# DS141-1_1-A.net
KiCad netlist of a schematic drawn in Altium Designer
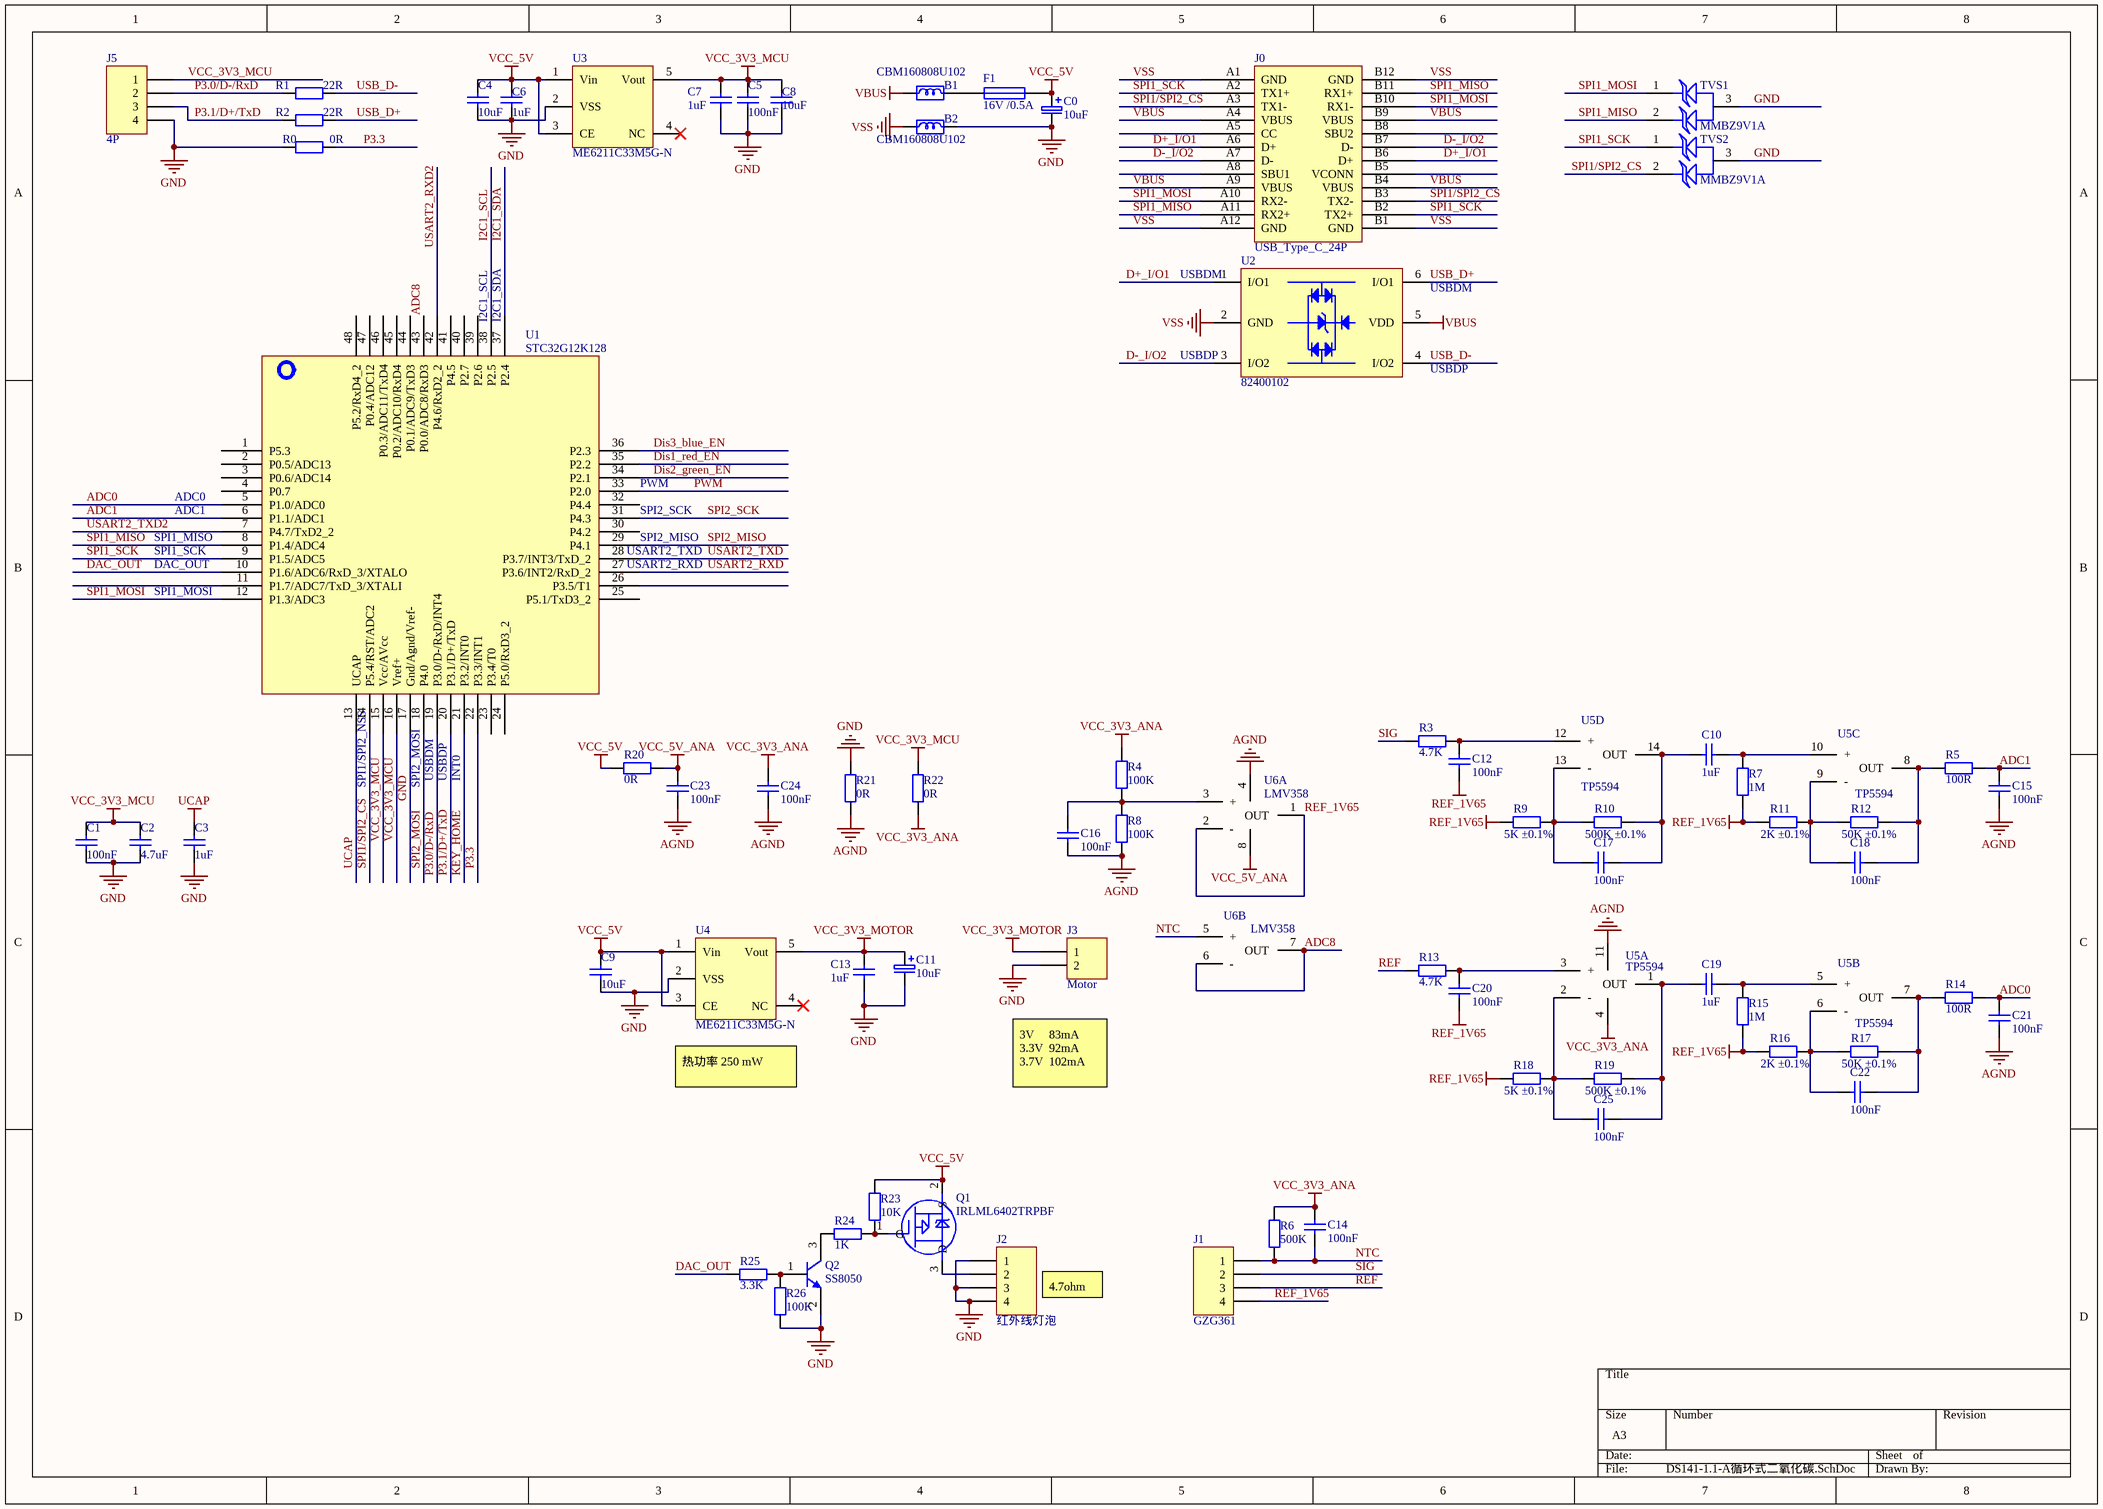
[diagram p0: DS141-1.1-A循环式二氧化碳.SchDoc]

(export (version "E")
  (design (tool "Eeschema 10.0.6"))
  (components
    (comp (ref "B1")
      (value "CBM160808U102")
      (footprint "0603Bead")
      (description "贴片磁珠")
      (libsource (lib "AD_SCH") (part "Chip Ferrite Bead 0606"))
    )
    (comp (ref "B2")
      (value "CBM160808U102")
      (footprint "0603Bead")
      (description "贴片磁珠")
      (libsource (lib "AD_SCH") (part "Chip Ferrite Bead 0606"))
    )
    (comp (ref "C0")
      (value "10uF")
      (footprint "AVX_3216-18(1206)_SMD")
      (description "钽电容")
      (fields (field (name "Comment") "AVX_10uF/16V ±10％(C106)"))
      (libsource (lib "AD_SCH") (part "AVX_10uF/16V ±10％(C106)"))
    )
    (comp (ref "C1")
      (value "100nF")
      (footprint "0603CAP")
      (description "贴片电容")
      (fields (field (name "Comment") "SMDCAP00013"))
      (libsource (lib "AD_SCH") (part "MLCC 100nF 50V ±10％ 0603"))
    )
    (comp (ref "C2")
      (value "4.7uF")
      (footprint "0603CAP")
      (description "贴片电容")
      (fields (field (name "Comment") "SMDCAP00012"))
      (libsource (lib "AD_SCH") (part "MLCC 4.7uF 50V ±10％ 0603"))
    )
    (comp (ref "C3")
      (value "1uF")
      (footprint "0603CAP")
      (description "贴片电容")
      (fields (field (name "Comment") "SMDCAP00015"))
      (libsource (lib "AD_SCH") (part "MLCC 1uF 50V ±10％ 0603"))
    )
    (comp (ref "C4")
      (value "10uF")
      (footprint "1206CAP")
      (description "贴片电容")
      (fields (field (name "Comment") "MLCC 10uF 50V ±20％ 1206"))
      (libsource (lib "AD_SCH") (part "MLCC 10uF 50V ±20％ 1206"))
    )
    (comp (ref "C5")
      (value "100nF")
      (footprint "0603CAP")
      (description "贴片电容")
      (fields (field (name "Comment") "SMDCAP00013"))
      (libsource (lib "AD_SCH") (part "MLCC 100nF 50V ±10％ 0603"))
    )
    (comp (ref "C6")
      (value "1uF")
      (footprint "0603CAP")
      (description "贴片电容")
      (fields (field (name "Comment") "SMDCAP00015"))
      (libsource (lib "AD_SCH") (part "MLCC 1uF 50V ±10％ 0603"))
    )
    (comp (ref "C7")
      (value "1uF")
      (footprint "0603CAP")
      (description "贴片电容")
      (fields (field (name "Comment") "SMDCAP00015"))
      (libsource (lib "AD_SCH") (part "MLCC 1uF 50V ±10％ 0603"))
    )
    (comp (ref "C8")
      (value "10uF")
      (footprint "1206CAP")
      (description "贴片电容")
      (fields (field (name "Comment") "MLCC 10uF 50V ±20％ 1206"))
      (libsource (lib "AD_SCH") (part "MLCC 10uF 50V ±20％ 1206"))
    )
    (comp (ref "C9")
      (value "10uF")
      (footprint "1206CAP")
      (description "贴片电容")
      (fields (field (name "Comment") "MLCC 10uF 50V ±20％ 1206"))
      (libsource (lib "AD_SCH") (part "MLCC 10uF 50V ±20％ 1206"))
    )
    (comp (ref "C10")
      (value "1uF")
      (footprint "0603CAP")
      (description "贴片电容")
      (fields (field (name "Comment") "SMDCAP00015"))
      (libsource (lib "AD_SCH") (part "MLCC 1uF 50V ±10％ 0603"))
    )
    (comp (ref "C11")
      (value "10uF")
      (footprint "AVX_3216-18(1206)_SMD")
      (description "钽电容")
      (fields (field (name "Comment") "AVX_10uF/16V ±10％(C106)"))
      (libsource (lib "AD_SCH") (part "AVX_10uF/16V ±10％(C106)"))
    )
    (comp (ref "C12")
      (value "100nF")
      (footprint "0603CAP")
      (description "贴片电容")
      (fields (field (name "Comment") "SMDCAP00013"))
      (libsource (lib "AD_SCH") (part "MLCC 100nF 50V ±10％ 0603"))
    )
    (comp (ref "C13")
      (value "1uF")
      (footprint "0603CAP")
      (description "贴片电容")
      (fields (field (name "Comment") "SMDCAP00015"))
      (libsource (lib "AD_SCH") (part "MLCC 1uF 50V ±10％ 0603"))
    )
    (comp (ref "C14")
      (value "100nF")
      (footprint "0603CAP")
      (description "贴片电容")
      (fields (field (name "Comment") "SMDCAP00013"))
      (libsource (lib "AD_SCH") (part "MLCC 100nF 50V ±10％ 0603"))
    )
    (comp (ref "C15")
      (value "100nF")
      (footprint "0603CAP")
      (description "贴片电容")
      (fields (field (name "Comment") "SMDCAP00013"))
      (libsource (lib "AD_SCH") (part "MLCC 100nF 50V ±10％ 0603"))
    )
    (comp (ref "C16")
      (value "100nF")
      (footprint "0603CAP")
      (description "贴片电容")
      (fields (field (name "Comment") "SMDCAP00013"))
      (libsource (lib "AD_SCH") (part "MLCC 100nF 50V ±10％ 0603"))
    )
    (comp (ref "C17")
      (value "100nF")
      (footprint "0603CAP")
      (description "贴片电容")
      (fields (field (name "Comment") "SMDCAP00013"))
      (libsource (lib "AD_SCH") (part "MLCC 100nF 50V ±10％ 0603"))
    )
    (comp (ref "C18")
      (value "100nF")
      (footprint "0603CAP")
      (description "贴片电容")
      (fields (field (name "Comment") "SMDCAP00013"))
      (libsource (lib "AD_SCH") (part "MLCC 100nF 50V ±10％ 0603"))
    )
    (comp (ref "C19")
      (value "1uF")
      (footprint "0603CAP")
      (description "贴片电容")
      (fields (field (name "Comment") "SMDCAP00015"))
      (libsource (lib "AD_SCH") (part "MLCC 1uF 50V ±10％ 0603"))
    )
    (comp (ref "C20")
      (value "100nF")
      (footprint "0603CAP")
      (description "贴片电容")
      (fields (field (name "Comment") "SMDCAP00013"))
      (libsource (lib "AD_SCH") (part "MLCC 100nF 50V ±10％ 0603"))
    )
    (comp (ref "C21")
      (value "100nF")
      (footprint "0603CAP")
      (description "贴片电容")
      (fields (field (name "Comment") "SMDCAP00013"))
      (libsource (lib "AD_SCH") (part "MLCC 100nF 50V ±10％ 0603"))
    )
    (comp (ref "C22")
      (value "100nF")
      (footprint "0603CAP")
      (description "贴片电容")
      (fields (field (name "Comment") "SMDCAP00013"))
      (libsource (lib "AD_SCH") (part "MLCC 100nF 50V ±10％ 0603"))
    )
    (comp (ref "C23")
      (value "100nF")
      (footprint "0603CAP")
      (description "贴片电容")
      (fields (field (name "Comment") "SMDCAP00013"))
      (libsource (lib "AD_SCH") (part "MLCC 100nF 50V ±10％ 0603"))
    )
    (comp (ref "C24")
      (value "100nF")
      (footprint "0603CAP")
      (description "贴片电容")
      (fields (field (name "Comment") "SMDCAP00013"))
      (libsource (lib "AD_SCH") (part "MLCC 100nF 50V ±10％ 0603"))
    )
    (comp (ref "C25")
      (value "100nF")
      (footprint "0603CAP")
      (description "贴片电容")
      (fields (field (name "Comment") "SMDCAP00013"))
      (libsource (lib "AD_SCH") (part "MLCC 100nF 50V ±10％ 0603"))
    )
    (comp (ref "F1")
      (value "16V /0.5A")
      (footprint "1206FUSE")
      (description "贴片自恢复保险丝 16V /0.5A")
      (fields (field (name "Comment") "SMD1206-050C-16V"))
      (libsource (lib "AD_SCH") (part "SMD1206-050C-16V"))
    )
    (comp (ref "J0")
      (value "USB_Type_C_24P")
      (footprint "USB_TYPE_C_24P_Receptacle")
      (libsource (lib "AD_SCH") (part "USB_Type_C_24P"))
    )
    (comp (ref "J1")
      (value "GZG361")
      (footprint "CO2_connecet_4p")
      (description "4P弯针座")
      (fields (field (name "Comment") "SL000000034"))
      (libsource (lib "AD_SCH") (part "XH2.54mm-4AW 弯针座"))
    )
    (comp (ref "J2")
      (value "红外线灯泡")
      (footprint "CO2_connecet_4p")
      (description "4P直针座")
      (fields (field (name "Comment") "SL000000029"))
      (libsource (lib "AD_SCH") (part "XH2.54mm-4A 直针座"))
    )
    (comp (ref "J3")
      (value "Motor")
      (footprint "SIP2")
      (description "单排直针")
      (fields (field (name "Comment") "SL000000042"))
      (libsource (lib "AD_SCH") (part "DIP2 单排直针 1*40P 间距2.54mm 针长11mm 铜"))
    )
    (comp (ref "J5")
      (value "4P")
      (footprint "H4")
      (description "单排直针")
      (fields (field (name "Comment") "DIP4单排直针  间距2mm 针长11mm 铜"))
      (libsource (lib "AD_SCH") (part "DIP4单排直针  间距2mm 针长11mm 铜"))
    )
    (comp (ref "Q1")
      (value "IRLML6402TRPBF")
      (footprint "SOT23")
      (description "贴片P-MOS管")
      (fields (field (name "Comment") "SMDPMOS00001"))
      (libsource (lib "AD_SCH") (part "IRLML6402TRPBF SOT-23 IR"))
    )
    (comp (ref "Q2")
      (value "SS8050")
      (footprint "SOT23")
      (description "贴片三极管")
      (fields (field (name "Comment") "SMDNPN00001"))
      (libsource (lib "AD_SCH") (part "SS8050 Y1 SOT-23"))
    )
    (comp (ref "R0")
      (value "0R")
      (footprint "0603RES")
      (description "贴片电阻")
      (fields (field (name "Comment") "Chip 0R 1/16W ±1％ 0603"))
      (libsource (lib "") (part "Chip 0R 1/16W ±1％ 0603_1"))
    )
    (comp (ref "R1")
      (value "22R")
      (footprint "0603RES")
      (description "贴片电阻")
      (fields (field (name "Comment") "Chip 22R 1/16W ±1％ 0603"))
      (libsource (lib "AD_SCH") (part "Chip 22R 1/16W ±1％ 0603"))
    )
    (comp (ref "R2")
      (value "22R")
      (footprint "0603RES")
      (description "贴片电阻")
      (fields (field (name "Comment") "Chip 22R 1/16W ±1％ 0603"))
      (libsource (lib "AD_SCH") (part "Chip 22R 1/16W ±1％ 0603"))
    )
    (comp (ref "R3")
      (value "4.7K")
      (footprint "0603RES")
      (description "贴片电阻")
      (fields (field (name "Comment") "SMDRES00047"))
      (libsource (lib "AD_SCH") (part "Chip 4.7K 1/10W ±1％ 0603"))
    )
    (comp (ref "R4")
      (value "100K")
      (footprint "0603RES")
      (description "贴片电阻")
      (fields (field (name "Comment") "SMDRES00071"))
      (libsource (lib "AD_SCH") (part "Chip 100K 1/16W ±1％ 0603"))
    )
    (comp (ref "R5")
      (value "100R")
      (footprint "0603RES")
      (description "贴片电阻")
      (fields (field (name "Comment") "SMDRES00015"))
      (libsource (lib "AD_SCH") (part "Chip 100R 1/16W ±1％ 0603"))
    )
    (comp (ref "R6")
      (value "500K")
      (footprint "0603RES")
      (fields (field (name "Comment") "Chip 500K 1/10W ±1% 0603"))
      (libsource (lib "AD_SCH") (part "Chip 500K 1/10W ±1% 0603"))
    )
    (comp (ref "R7")
      (value "1M")
      (footprint "0603RES")
      (description "贴片电阻")
      (fields (field (name "Comment") "SMDRES00085"))
      (libsource (lib "AD_SCH") (part "Chip 1M 1/16W ±1％ 0603"))
    )
    (comp (ref "R8")
      (value "100K")
      (footprint "0603RES")
      (description "贴片电阻")
      (fields (field (name "Comment") "SMDRES00071"))
      (libsource (lib "AD_SCH") (part "Chip 100K 1/16W ±1％ 0603"))
    )
    (comp (ref "R9")
      (value "5K ±0.1%")
      (footprint "0603RES")
      (fields (field (name "Comment") "Chip 5K 1/10W ±0.1％ 0603"))
      (libsource (lib "AD_SCH") (part "Chip 5K 1/10W ±0.1％ 0603"))
    )
    (comp (ref "R10")
      (value "500K ±0.1%")
      (footprint "0603RES")
      (fields (field (name "Comment") "Chip 500K 1/10W ±0.1% 0603"))
      (libsource (lib "AD_SCH") (part "Chip 500K 1/10W ±0.1% 0603"))
    )
    (comp (ref "R11")
      (value "2K ±0.1%")
      (footprint "0603RES")
      (fields (field (name "Comment") "Chip 2K 1/10W ±0.1％ 0603"))
      (libsource (lib "AD_SCH") (part "Chip 2K 1/10W ±0.1％ 0603"))
    )
    (comp (ref "R12")
      (value "50K ±0.1%")
      (footprint "0603RES")
      (fields (field (name "Comment") "Chip 50K 1/10W ±0.1％ 0603"))
      (libsource (lib "AD_SCH") (part "Chip 50K 1/10W ±0.1％ 0603"))
    )
    (comp (ref "R13")
      (value "4.7K")
      (footprint "0603RES")
      (description "贴片电阻")
      (fields (field (name "Comment") "SMDRES00047"))
      (libsource (lib "AD_SCH") (part "Chip 4.7K 1/10W ±1％ 0603"))
    )
    (comp (ref "R14")
      (value "100R")
      (footprint "0603RES")
      (description "贴片电阻")
      (fields (field (name "Comment") "SMDRES00015"))
      (libsource (lib "AD_SCH") (part "Chip 100R 1/16W ±1％ 0603"))
    )
    (comp (ref "R15")
      (value "1M")
      (footprint "0603RES")
      (description "贴片电阻")
      (fields (field (name "Comment") "SMDRES00085"))
      (libsource (lib "AD_SCH") (part "Chip 1M 1/16W ±1％ 0603"))
    )
    (comp (ref "R16")
      (value "2K ±0.1%")
      (footprint "0603RES")
      (fields (field (name "Comment") "Chip 2K 1/10W ±0.1％ 0603"))
      (libsource (lib "AD_SCH") (part "Chip 2K 1/10W ±0.1％ 0603"))
    )
    (comp (ref "R17")
      (value "50K ±0.1%")
      (footprint "0603RES")
      (fields (field (name "Comment") "Chip 50K 1/10W ±0.1％ 0603"))
      (libsource (lib "AD_SCH") (part "Chip 50K 1/10W ±0.1％ 0603"))
    )
    (comp (ref "R18")
      (value "5K ±0.1%")
      (footprint "0603RES")
      (fields (field (name "Comment") "Chip 5K 1/10W ±0.1％ 0603"))
      (libsource (lib "AD_SCH") (part "Chip 5K 1/10W ±0.1％ 0603"))
    )
    (comp (ref "R19")
      (value "500K ±0.1%")
      (footprint "0603RES")
      (fields (field (name "Comment") "Chip 500K 1/10W ±0.1% 0603"))
      (libsource (lib "AD_SCH") (part "Chip 500K 1/10W ±0.1% 0603"))
    )
    (comp (ref "R20")
      (value "0R")
      (footprint "0603RES")
      (description "贴片电阻")
      (fields (field (name "Comment") "Chip 0R 1/16W ±1％ 0603"))
      (libsource (lib "") (part "Chip 0R 1/16W ±1％ 0603_1"))
    )
    (comp (ref "R21")
      (value "0R")
      (footprint "0603RES")
      (description "贴片电阻")
      (fields (field (name "Comment") "Chip 0R 1/16W ±1％ 0603"))
      (libsource (lib "AD_SCH") (part "Chip 0R 1/16W ±1％ 0603"))
    )
    (comp (ref "R22")
      (value "0R")
      (footprint "0603RES")
      (description "贴片电阻")
      (fields (field (name "Comment") "Chip 0R 1/16W ±1％ 0603"))
      (libsource (lib "AD_SCH") (part "Chip 0R 1/16W ±1％ 0603"))
    )
    (comp (ref "R23")
      (value "10K")
      (footprint "0603RES")
      (description "贴片电阻")
      (fields (field (name "Comment") "SMDRES00056"))
      (libsource (lib "AD_SCH") (part "Chip 10K 1/16W ±1％ 0603"))
    )
    (comp (ref "R24")
      (value "1K")
      (footprint "0603RES")
      (description "贴片电阻")
      (fields (field (name "Comment") "SMDRES00034"))
      (libsource (lib "AD_SCH") (part "Chip 1K 1/16W ±1％ 0603"))
    )
    (comp (ref "R25")
      (value "3.3K")
      (footprint "0603RES")
      (description "贴片电阻")
      (fields (field (name "Comment") "SMDRES00090"))
      (libsource (lib "AD_SCH") (part "Chip 3.3K 1/16W ±1％ 0603"))
    )
    (comp (ref "R26")
      (value "100K")
      (footprint "0603RES")
      (description "贴片电阻")
      (fields (field (name "Comment") "SMDRES00071"))
      (libsource (lib "") (part "Chip 100K 1/16W ±1％ 0603_1"))
    )
    (comp (ref "TVS1")
      (value "MMBZ9V1A")
      (footprint "SOT23")
      (description "瞬态抑制二极管")
      (libsource (lib "AD_SCH") (part "TVS"))
    )
    (comp (ref "TVS2")
      (value "MMBZ9V1A")
      (footprint "SOT23")
      (description "瞬态抑制二极管")
      (libsource (lib "AD_SCH") (part "TVS"))
    )
    (comp (ref "U1")
      (value "STC32G12K128")
      (footprint "LQFP-48")
      (description "单片机芯片")
      (fields (field (name "Comment") "STC32G12K128_35I LQFP48"))
      (libsource (lib "AD_SCH") (part "STC32G12K128_35I LQFP48"))
    )
    (comp (ref "U2")
      (value "82400102")
      (footprint "SOT23-6")
      (description "瞬态抑制二极管(TVS)")
      (libsource (lib "AD_SCH") (part "82400102"))
    )
    (comp (ref "U3")
      (value "ME6211C33M5G-N")
      (footprint "SOT23-5")
      (description "稳压芯片")
      (libsource (lib "AD_SCH") (part "ME6211C33M5G-N"))
    )
    (comp (ref "U4")
      (value "ME6211C33M5G-N")
      (footprint "SOT23-5")
      (description "稳压芯片")
      (libsource (lib "AD_SCH") (part "ME6211C33M5G-N"))
    )
    (comp (ref "U5")
      (value "TP5594")
      (footprint "TSSOP14")
      (fields (field (name "Comment") "TP5594-TR  TSSOP-14"))
      (libsource (lib "AD_SCH") (part "TP5594-TR  TSSOP-14"))
    )
    (comp (ref "U6")
      (value "LMV358")
      (footprint "VSSOP-8-H-1.1")
      (description "双路、5.5V、1MHz、4mV 失调电压、RRO 运算放大器")
      (fields (field (name "Comment") "LMV358IDGKR  VSSOP-8"))
      (libsource (lib "AD_SCH") (part "LMV358IDGKR  VSSOP-8"))
    )
  )
  (nets
    (net (code "1") (name "/ADC0") (class "Default")
      (node (ref "C21") (pin "1") (pinfunction "1_1") (pintype "passive"))
      (node (ref "R14") (pin "2") (pinfunction "2_2") (pintype "passive"))
      (node (ref "U1") (pin "5") (pinfunction "P1.0/ADC0_5") (pintype "passive"))
    )
    (net (code "2") (name "/ADC1") (class "Default")
      (node (ref "C15") (pin "1") (pinfunction "1_1") (pintype "passive"))
      (node (ref "R5") (pin "2") (pinfunction "2_2") (pintype "passive"))
      (node (ref "U1") (pin "6") (pinfunction "P1.1/ADC1_6") (pintype "passive"))
    )
    (net (code "3") (name "/ADC8") (class "Default")
      (node (ref "U1") (pin "43") (pinfunction "P0.0/ADC8/RxD3_43") (pintype "passive"))
      (node (ref "U6") (pin "6") (pinfunction "-_6") (pintype "passive"))
      (node (ref "U6") (pin "7") (pinfunction "OUT_7") (pintype "passive"))
    )
    (net (code "4") (name "/D+_I{slash}O1") (class "Default")
      (node (ref "J0") (pin "A6") (pinfunction "D+_A6") (pintype "passive"))
      (node (ref "J0") (pin "B6") (pinfunction "D+_B6") (pintype "passive"))
      (node (ref "U2") (pin "1") (pinfunction "I/O1_1") (pintype "passive"))
    )
    (net (code "5") (name "/D-_I{slash}O2") (class "Default")
      (node (ref "J0") (pin "A7") (pinfunction "D-_A7") (pintype "passive"))
      (node (ref "J0") (pin "B7") (pinfunction "D-_B7") (pintype "passive"))
      (node (ref "U2") (pin "3") (pinfunction "I/O2_3") (pintype "passive"))
    )
    (net (code "6") (name "/DAC_OUT") (class "Default")
      (node (ref "R25") (pin "2") (pinfunction "2_2") (pintype "passive"))
      (node (ref "U1") (pin "10") (pinfunction "P1.6/ADC6/RxD_3/XTALO_10") (pintype "passive"))
    )
    (net (code "7") (name "/Dis1_red_EN") (class "Default")
      (node (ref "U1") (pin "35") (pinfunction "P2.2_35") (pintype "passive"))
    )
    (net (code "8") (name "/Dis2_green_EN") (class "Default")
      (node (ref "U1") (pin "34") (pinfunction "P2.1_34") (pintype "passive"))
    )
    (net (code "9") (name "/Dis3_blue_EN") (class "Default")
      (node (ref "U1") (pin "36") (pinfunction "P2.3_36") (pintype "passive"))
    )
    (net (code "10") (name "/I2C1_SCL") (class "Default")
      (node (ref "U1") (pin "38") (pinfunction "P2.5_38") (pintype "passive"))
    )
    (net (code "11") (name "/I2C1_SDA") (class "Default")
      (node (ref "U1") (pin "37") (pinfunction "P2.4_37") (pintype "passive"))
    )
    (net (code "12") (name "/KEY_HOME") (class "Default")
      (node (ref "U1") (pin "21") (pinfunction "P3.2/INT0_21") (pintype "passive"))
    )
    (net (code "13") (name "/NTC") (class "Default")
      (node (ref "C14") (pin "1") (pinfunction "1_1") (pintype "passive"))
      (node (ref "J1") (pin "1") (pinfunction "1_1") (pintype "passive"))
      (node (ref "R6") (pin "1") (pinfunction "1_1") (pintype "passive"))
      (node (ref "U6") (pin "5") (pinfunction "+_5") (pintype "passive"))
    )
    (net (code "14") (name "/P3.0{slash}D-{slash}RxD") (class "Default")
      (node (ref "J5") (pin "2") (pinfunction "2_2") (pintype "passive"))
      (node (ref "R1") (pin "1") (pinfunction "1_1") (pintype "passive"))
      (node (ref "U1") (pin "19") (pinfunction "P3.0/D-/RxD/INT4_19") (pintype "passive"))
    )
    (net (code "15") (name "/P3.1{slash}D+{slash}TxD") (class "Default")
      (node (ref "J5") (pin "3") (pinfunction "3_3") (pintype "passive"))
      (node (ref "R2") (pin "1") (pinfunction "1_1") (pintype "passive"))
      (node (ref "U1") (pin "20") (pinfunction "P3.1/D+/TxD_20") (pintype "passive"))
    )
    (net (code "16") (name "/P3.3") (class "Default")
      (node (ref "R0") (pin "2") (pinfunction "2_2") (pintype "passive"))
      (node (ref "U1") (pin "22") (pinfunction "P3.3/INT1_22") (pintype "passive"))
    )
    (net (code "17") (name "/PWM") (class "Default")
      (node (ref "U1") (pin "33") (pinfunction "P2.0_33") (pintype "passive"))
    )
    (net (code "18") (name "/REF") (class "Default")
      (node (ref "J1") (pin "3") (pinfunction "3_3") (pintype "passive"))
      (node (ref "R13") (pin "1") (pinfunction "1_1") (pintype "passive"))
    )
    (net (code "19") (name "/SIG") (class "Default")
      (node (ref "J1") (pin "2") (pinfunction "2_2") (pintype "passive"))
      (node (ref "R3") (pin "1") (pinfunction "1_1") (pintype "passive"))
    )
    (net (code "20") (name "/SPI1_MISO") (class "Default")
      (node (ref "J0") (pin "A11") (pinfunction "RX2+_A11") (pintype "passive"))
      (node (ref "J0") (pin "B11") (pinfunction "RX1+_B11") (pintype "passive"))
      (node (ref "TVS1") (pin "2") (pinfunction "2_2") (pintype "passive"))
      (node (ref "U1") (pin "8") (pinfunction "P1.4/ADC4_8") (pintype "passive"))
    )
    (net (code "21") (name "/SPI1_MOSI") (class "Default")
      (node (ref "J0") (pin "A10") (pinfunction "RX2-_A10") (pintype "passive"))
      (node (ref "J0") (pin "B10") (pinfunction "RX1-_B10") (pintype "passive"))
      (node (ref "TVS1") (pin "1") (pinfunction "1_1") (pintype "passive"))
      (node (ref "U1") (pin "12") (pinfunction "P1.3/ADC3_12") (pintype "passive"))
    )
    (net (code "22") (name "/SPI1_SCK") (class "Default")
      (node (ref "J0") (pin "A2") (pinfunction "TX1+_A2") (pintype "passive"))
      (node (ref "J0") (pin "B2") (pinfunction "TX2+_B2") (pintype "passive"))
      (node (ref "TVS2") (pin "1") (pinfunction "1_1") (pintype "passive"))
      (node (ref "U1") (pin "9") (pinfunction "P1.5/ADC5_9") (pintype "passive"))
    )
    (net (code "23") (name "/SPI1{slash}SPI2_CS") (class "Default")
      (node (ref "J0") (pin "A3") (pinfunction "TX1-_A3") (pintype "passive"))
      (node (ref "J0") (pin "B3") (pinfunction "TX2-_B3") (pintype "passive"))
      (node (ref "TVS2") (pin "2") (pinfunction "2_2") (pintype "passive"))
      (node (ref "U1") (pin "14") (pinfunction "P5.4/RST/ADC2_14") (pintype "passive"))
    )
    (net (code "24") (name "/SPI2_MISO") (class "Default")
      (node (ref "U1") (pin "29") (pinfunction "P4.1_29") (pintype "passive"))
    )
    (net (code "25") (name "/SPI2_MOSI") (class "Default")
      (node (ref "U1") (pin "18") (pinfunction "P4.0_18") (pintype "passive"))
    )
    (net (code "26") (name "/SPI2_SCK") (class "Default")
      (node (ref "U1") (pin "31") (pinfunction "P4.3_31") (pintype "passive"))
    )
    (net (code "27") (name "/USART2_RXD") (class "Default")
      (node (ref "U1") (pin "27") (pinfunction "P3.6/INT2/RxD_2_27") (pintype "passive"))
    )
    (net (code "28") (name "/USART2_RXD2") (class "Default")
      (node (ref "U1") (pin "42") (pinfunction "P4.6/RxD2_2_42") (pintype "passive"))
    )
    (net (code "29") (name "/USART2_TXD") (class "Default")
      (node (ref "U1") (pin "28") (pinfunction "P3.7/INT3/TxD_2_28") (pintype "passive"))
    )
    (net (code "30") (name "/USART2_TXD2") (class "Default")
      (node (ref "U1") (pin "7") (pinfunction "P4.7/TxD2_2_7") (pintype "passive"))
    )
    (net (code "31") (name "/USB_D+") (class "Default")
      (node (ref "R2") (pin "2") (pinfunction "2_2") (pintype "passive"))
      (node (ref "U2") (pin "6") (pinfunction "I/O1_6") (pintype "passive"))
    )
    (net (code "32") (name "/USB_D-") (class "Default")
      (node (ref "R1") (pin "2") (pinfunction "2_2") (pintype "passive"))
      (node (ref "U2") (pin "4") (pinfunction "I/O2_4") (pintype "passive"))
    )
    (net (code "33") (name "AGND") (class "Default")
      (node (ref "C15") (pin "2") (pinfunction "2_2") (pintype "passive"))
      (node (ref "C16") (pin "1") (pinfunction "1_1") (pintype "passive"))
      (node (ref "C21") (pin "2") (pinfunction "2_2") (pintype "passive"))
      (node (ref "C23") (pin "1") (pinfunction "1_1") (pintype "passive"))
      (node (ref "C24") (pin "1") (pinfunction "1_1") (pintype "passive"))
      (node (ref "R21") (pin "2") (pinfunction "2_2") (pintype "passive"))
      (node (ref "R8") (pin "1") (pinfunction "1_1") (pintype "passive"))
      (node (ref "U5") (pin "11") (pinfunction "GND_11") (pintype "passive"))
      (node (ref "U6") (pin "4") (pinfunction "GND_4") (pintype "passive"))
    )
    (net (code "34") (name "GND") (class "Default")
      (node (ref "B2") (pin "2") (pinfunction "2_2") (pintype "passive"))
      (node (ref "C0") (pin "2") (pinfunction "2_2") (pintype "passive"))
      (node (ref "C1") (pin "1") (pinfunction "1_1") (pintype "passive"))
      (node (ref "C11") (pin "2") (pinfunction "2_2") (pintype "passive"))
      (node (ref "C13") (pin "1") (pinfunction "1_1") (pintype "passive"))
      (node (ref "C2") (pin "1") (pinfunction "1_1") (pintype "passive"))
      (node (ref "C3") (pin "1") (pinfunction "1_1") (pintype "passive"))
      (node (ref "C4") (pin "1") (pinfunction "1_1") (pintype "passive"))
      (node (ref "C5") (pin "1") (pinfunction "1_1") (pintype "passive"))
      (node (ref "C6") (pin "1") (pinfunction "1_1") (pintype "passive"))
      (node (ref "C7") (pin "1") (pinfunction "1_1") (pintype "passive"))
      (node (ref "C8") (pin "1") (pinfunction "1_1") (pintype "passive"))
      (node (ref "C9") (pin "1") (pinfunction "1_1") (pintype "passive"))
      (node (ref "J2") (pin "1") (pinfunction "1_1") (pintype "passive"))
      (node (ref "J2") (pin "3") (pinfunction "3_3") (pintype "passive"))
      (node (ref "J2") (pin "4") (pinfunction "4_4") (pintype "passive"))
      (node (ref "J3") (pin "2") (pinfunction "2_2") (pintype "passive"))
      (node (ref "J5") (pin "4") (pinfunction "4_4") (pintype "passive"))
      (node (ref "Q2") (pin "2") (pinfunction "E_2") (pintype "passive"))
      (node (ref "R0") (pin "1") (pinfunction "1_1") (pintype "passive"))
      (node (ref "R21") (pin "1") (pinfunction "1_1") (pintype "passive"))
      (node (ref "R26") (pin "2") (pinfunction "2_2") (pintype "passive"))
      (node (ref "TVS1") (pin "3") (pinfunction "3_3") (pintype "passive"))
      (node (ref "TVS2") (pin "3") (pinfunction "3_3") (pintype "passive"))
      (node (ref "U1") (pin "17") (pinfunction "Gnd/Agnd/Vref-_17") (pintype "passive"))
      (node (ref "U3") (pin "2") (pinfunction "VSS_2") (pintype "passive"))
      (node (ref "U4") (pin "2") (pinfunction "VSS_2") (pintype "passive"))
    )
    (net (code "35") (name "Net-(B1-Pad2)") (class "Default")
      (node (ref "B1") (pin "2") (pinfunction "2_2") (pintype "passive"))
      (node (ref "F1") (pin "1") (pinfunction "1_1") (pintype "passive"))
    )
    (net (code "36") (name "Net-(Q1-D)") (class "Default")
      (node (ref "J2") (pin "2") (pinfunction "2_2") (pintype "passive"))
      (node (ref "Q1") (pin "3") (pinfunction "D_3") (pintype "passive"))
    )
    (net (code "37") (name "Net-(Q1-G)") (class "Default")
      (node (ref "Q1") (pin "1") (pinfunction "G_1") (pintype "passive"))
      (node (ref "R23") (pin "2") (pinfunction "2_2") (pintype "passive"))
      (node (ref "R24") (pin "2") (pinfunction "2_2") (pintype "passive"))
    )
    (net (code "38") (name "Net-(Q2-B)") (class "Default")
      (node (ref "Q2") (pin "1") (pinfunction "B_1") (pintype "passive"))
      (node (ref "R25") (pin "1") (pinfunction "1_1") (pintype "passive"))
      (node (ref "R26") (pin "1") (pinfunction "1_1") (pintype "passive"))
    )
    (net (code "39") (name "Net-(Q2-C)") (class "Default")
      (node (ref "Q2") (pin "3") (pinfunction "C_3") (pintype "passive"))
      (node (ref "R24") (pin "1") (pinfunction "1_1") (pintype "passive"))
    )
    (net (code "40") (name "Net-(U5A-+)") (class "Default")
      (node (ref "C20") (pin "1") (pinfunction "1_1") (pintype "passive"))
      (node (ref "R13") (pin "2") (pinfunction "2_2") (pintype "passive"))
      (node (ref "U5") (pin "3") (pinfunction "+_3") (pintype "passive"))
    )
    (net (code "41") (name "Net-(U5A--)") (class "Default")
      (node (ref "C25") (pin "1") (pinfunction "1_1") (pintype "passive"))
      (node (ref "R18") (pin "2") (pinfunction "2_2") (pintype "passive"))
      (node (ref "R19") (pin "1") (pinfunction "1_1") (pintype "passive"))
      (node (ref "U5") (pin "2") (pinfunction "-_2") (pintype "passive"))
    )
    (net (code "42") (name "Net-(U5A-OUT)") (class "Default")
      (node (ref "C19") (pin "1") (pinfunction "1_1") (pintype "passive"))
      (node (ref "C25") (pin "2") (pinfunction "2_2") (pintype "passive"))
      (node (ref "R19") (pin "2") (pinfunction "2_2") (pintype "passive"))
      (node (ref "U5") (pin "1") (pinfunction "OUT_1") (pintype "passive"))
    )
    (net (code "43") (name "Net-(U5B-+)") (class "Default")
      (node (ref "C19") (pin "2") (pinfunction "2_2") (pintype "passive"))
      (node (ref "R15") (pin "2") (pinfunction "2_2") (pintype "passive"))
      (node (ref "U5") (pin "5") (pinfunction "+_5") (pintype "passive"))
    )
    (net (code "44") (name "Net-(U5B--)") (class "Default")
      (node (ref "C22") (pin "1") (pinfunction "1_1") (pintype "passive"))
      (node (ref "R16") (pin "1") (pinfunction "1_1") (pintype "passive"))
      (node (ref "R17") (pin "1") (pinfunction "1_1") (pintype "passive"))
      (node (ref "U5") (pin "6") (pinfunction "-_6") (pintype "passive"))
    )
    (net (code "45") (name "Net-(U5B-OUT)") (class "Default")
      (node (ref "C22") (pin "2") (pinfunction "2_2") (pintype "passive"))
      (node (ref "R14") (pin "1") (pinfunction "1_1") (pintype "passive"))
      (node (ref "R17") (pin "2") (pinfunction "2_2") (pintype "passive"))
      (node (ref "U5") (pin "7") (pinfunction "OUT_7") (pintype "passive"))
    )
    (net (code "46") (name "Net-(U5C-+)") (class "Default")
      (node (ref "C10") (pin "2") (pinfunction "2_2") (pintype "passive"))
      (node (ref "R7") (pin "2") (pinfunction "2_2") (pintype "passive"))
      (node (ref "U5") (pin "10") (pinfunction "+_10") (pintype "passive"))
    )
    (net (code "47") (name "Net-(U5C--)") (class "Default")
      (node (ref "C18") (pin "1") (pinfunction "1_1") (pintype "passive"))
      (node (ref "R11") (pin "1") (pinfunction "1_1") (pintype "passive"))
      (node (ref "R12") (pin "1") (pinfunction "1_1") (pintype "passive"))
      (node (ref "U5") (pin "9") (pinfunction "-_9") (pintype "passive"))
    )
    (net (code "48") (name "Net-(U5C-OUT)") (class "Default")
      (node (ref "C18") (pin "2") (pinfunction "2_2") (pintype "passive"))
      (node (ref "R12") (pin "2") (pinfunction "2_2") (pintype "passive"))
      (node (ref "R5") (pin "1") (pinfunction "1_1") (pintype "passive"))
      (node (ref "U5") (pin "8") (pinfunction "OUT_8") (pintype "passive"))
    )
    (net (code "49") (name "Net-(U5D-+)") (class "Default")
      (node (ref "C12") (pin "1") (pinfunction "1_1") (pintype "passive"))
      (node (ref "R3") (pin "2") (pinfunction "2_2") (pintype "passive"))
      (node (ref "U5") (pin "12") (pinfunction "+_12") (pintype "passive"))
    )
    (net (code "50") (name "Net-(U5D--)") (class "Default")
      (node (ref "C17") (pin "1") (pinfunction "1_1") (pintype "passive"))
      (node (ref "R10") (pin "1") (pinfunction "1_1") (pintype "passive"))
      (node (ref "R9") (pin "2") (pinfunction "2_2") (pintype "passive"))
      (node (ref "U5") (pin "13") (pinfunction "-_13") (pintype "passive"))
    )
    (net (code "51") (name "Net-(U5D-OUT)") (class "Default")
      (node (ref "C10") (pin "1") (pinfunction "1_1") (pintype "passive"))
      (node (ref "C17") (pin "2") (pinfunction "2_2") (pintype "passive"))
      (node (ref "R10") (pin "2") (pinfunction "2_2") (pintype "passive"))
      (node (ref "U5") (pin "14") (pinfunction "OUT_14") (pintype "passive"))
    )
    (net (code "52") (name "Net-(U6A-+)") (class "Default")
      (node (ref "C16") (pin "2") (pinfunction "2_2") (pintype "passive"))
      (node (ref "R4") (pin "1") (pinfunction "1_1") (pintype "passive"))
      (node (ref "R8") (pin "2") (pinfunction "2_2") (pintype "passive"))
      (node (ref "U6") (pin "3") (pinfunction "+_3") (pintype "passive"))
    )
    (net (code "53") (name "REF_1V65") (class "Default")
      (node (ref "C12") (pin "2") (pinfunction "2_2") (pintype "passive"))
      (node (ref "C20") (pin "2") (pinfunction "2_2") (pintype "passive"))
      (node (ref "J1") (pin "4") (pinfunction "4_4") (pintype "passive"))
      (node (ref "R11") (pin "2") (pinfunction "2_2") (pintype "passive"))
      (node (ref "R15") (pin "1") (pinfunction "1_1") (pintype "passive"))
      (node (ref "R16") (pin "2") (pinfunction "2_2") (pintype "passive"))
      (node (ref "R18") (pin "1") (pinfunction "1_1") (pintype "passive"))
      (node (ref "R7") (pin "1") (pinfunction "1_1") (pintype "passive"))
      (node (ref "R9") (pin "1") (pinfunction "1_1") (pintype "passive"))
      (node (ref "U6") (pin "1") (pinfunction "OUT_1") (pintype "passive"))
      (node (ref "U6") (pin "2") (pinfunction "-_2") (pintype "passive"))
    )
    (net (code "54") (name "UCAP") (class "Default")
      (node (ref "C3") (pin "2") (pinfunction "2_2") (pintype "passive"))
      (node (ref "U1") (pin "13") (pinfunction "UCAP_13") (pintype "passive"))
    )
    (net (code "55") (name "VBUS") (class "Default")
      (node (ref "B1") (pin "1") (pinfunction "1_1") (pintype "passive"))
      (node (ref "J0") (pin "A4") (pinfunction "VBUS_A4") (pintype "passive"))
      (node (ref "J0") (pin "A9") (pinfunction "VBUS_A9") (pintype "passive"))
      (node (ref "J0") (pin "B4") (pinfunction "VBUS_B4") (pintype "passive"))
      (node (ref "J0") (pin "B9") (pinfunction "VBUS_B9") (pintype "passive"))
      (node (ref "U2") (pin "5") (pinfunction "VDD_5") (pintype "passive"))
    )
    (net (code "56") (name "VCC_3V3_ANA") (class "Default")
      (node (ref "C14") (pin "2") (pinfunction "2_2") (pintype "passive"))
      (node (ref "C24") (pin "2") (pinfunction "2_2") (pintype "passive"))
      (node (ref "R22") (pin "2") (pinfunction "2_2") (pintype "passive"))
      (node (ref "R4") (pin "2") (pinfunction "2_2") (pintype "passive"))
      (node (ref "R6") (pin "2") (pinfunction "2_2") (pintype "passive"))
      (node (ref "U5") (pin "4") (pinfunction "VSS_4") (pintype "passive"))
    )
    (net (code "57") (name "VCC_3V3_MCU") (class "Default")
      (node (ref "C1") (pin "2") (pinfunction "2_2") (pintype "passive"))
      (node (ref "C2") (pin "2") (pinfunction "2_2") (pintype "passive"))
      (node (ref "C5") (pin "2") (pinfunction "2_2") (pintype "passive"))
      (node (ref "C7") (pin "2") (pinfunction "2_2") (pintype "passive"))
      (node (ref "C8") (pin "2") (pinfunction "2_2") (pintype "passive"))
      (node (ref "J5") (pin "1") (pinfunction "1_1") (pintype "passive"))
      (node (ref "R22") (pin "1") (pinfunction "1_1") (pintype "passive"))
      (node (ref "U1") (pin "15") (pinfunction "Vcc/AVcc_15") (pintype "passive"))
      (node (ref "U1") (pin "16") (pinfunction "Vref+_16") (pintype "passive"))
      (node (ref "U3") (pin "5") (pinfunction "Vout_5") (pintype "passive"))
    )
    (net (code "58") (name "VCC_3V3_MOTOR") (class "Default")
      (node (ref "C11") (pin "1") (pinfunction "1_1") (pintype "passive"))
      (node (ref "C13") (pin "2") (pinfunction "2_2") (pintype "passive"))
      (node (ref "J3") (pin "1") (pinfunction "1_1") (pintype "passive"))
      (node (ref "U4") (pin "5") (pinfunction "Vout_5") (pintype "passive"))
    )
    (net (code "59") (name "VCC_5V") (class "Default")
      (node (ref "C0") (pin "1") (pinfunction "1_1") (pintype "passive"))
      (node (ref "C4") (pin "2") (pinfunction "2_2") (pintype "passive"))
      (node (ref "C6") (pin "2") (pinfunction "2_2") (pintype "passive"))
      (node (ref "C9") (pin "2") (pinfunction "2_2") (pintype "passive"))
      (node (ref "F1") (pin "2") (pinfunction "2_2") (pintype "passive"))
      (node (ref "Q1") (pin "2") (pinfunction "S_2") (pintype "passive"))
      (node (ref "R20") (pin "1") (pinfunction "1_1") (pintype "passive"))
      (node (ref "R23") (pin "1") (pinfunction "1_1") (pintype "passive"))
      (node (ref "U3") (pin "1") (pinfunction "Vin_1") (pintype "passive"))
      (node (ref "U3") (pin "3") (pinfunction "CE_3") (pintype "passive"))
      (node (ref "U4") (pin "1") (pinfunction "Vin_1") (pintype "passive"))
      (node (ref "U4") (pin "3") (pinfunction "CE_3") (pintype "passive"))
    )
    (net (code "60") (name "VCC_5V_ANA") (class "Default")
      (node (ref "C23") (pin "2") (pinfunction "2_2") (pintype "passive"))
      (node (ref "R20") (pin "2") (pinfunction "2_2") (pintype "passive"))
      (node (ref "U6") (pin "8") (pinfunction "VCC_8") (pintype "passive"))
    )
    (net (code "61") (name "VSS") (class "Default")
      (node (ref "B2") (pin "1") (pinfunction "1_1") (pintype "passive"))
      (node (ref "J0") (pin "A1") (pinfunction "GND_A1") (pintype "passive"))
      (node (ref "J0") (pin "A12") (pinfunction "GND_A12") (pintype "passive"))
      (node (ref "J0") (pin "B1") (pinfunction "GND_B1") (pintype "passive"))
      (node (ref "J0") (pin "B12") (pinfunction "GND_B12") (pintype "passive"))
      (node (ref "U2") (pin "2") (pinfunction "GND_2") (pintype "passive"))
    )
    (net (code "62") (name "unconnected-(J0-CC-PadA5)") (class "Default")
      (node (ref "J0") (pin "A5") (pinfunction "CC_A5") (pintype "passive"))
    )
    (net (code "63") (name "unconnected-(J0-SBU1-PadA8)") (class "Default")
      (node (ref "J0") (pin "A8") (pinfunction "SBU1_A8") (pintype "passive"))
    )
    (net (code "64") (name "unconnected-(J0-SBU2-PadB8)") (class "Default")
      (node (ref "J0") (pin "B8") (pinfunction "SBU2_B8") (pintype "passive"))
    )
    (net (code "65") (name "unconnected-(J0-VCONN-PadB5)") (class "Default")
      (node (ref "J0") (pin "B5") (pinfunction "VCONN_B5") (pintype "passive"))
    )
    (net (code "66") (name "unconnected-(U1-P0.1{slash}ADC9{slash}TxD3-Pad44)") (class "Default")
      (node (ref "U1") (pin "44") (pinfunction "P0.1/ADC9/TxD3_44") (pintype "passive"))
    )
    (net (code "67") (name "unconnected-(U1-P0.2{slash}ADC10{slash}RxD4-Pad45)") (class "Default")
      (node (ref "U1") (pin "45") (pinfunction "P0.2/ADC10/RxD4_45") (pintype "passive"))
    )
    (net (code "68") (name "unconnected-(U1-P0.3{slash}ADC11{slash}TxD4-Pad46)") (class "Default")
      (node (ref "U1") (pin "46") (pinfunction "P0.3/ADC11/TxD4_46") (pintype "passive"))
    )
    (net (code "69") (name "unconnected-(U1-P0.4{slash}ADC12-Pad47)") (class "Default")
      (node (ref "U1") (pin "47") (pinfunction "P0.4/ADC12_47") (pintype "passive"))
    )
    (net (code "70") (name "unconnected-(U1-P0.5{slash}ADC13-Pad2)") (class "Default")
      (node (ref "U1") (pin "2") (pinfunction "P0.5/ADC13_2") (pintype "passive"))
    )
    (net (code "71") (name "unconnected-(U1-P0.6{slash}ADC14-Pad3)") (class "Default")
      (node (ref "U1") (pin "3") (pinfunction "P0.6/ADC14_3") (pintype "passive"))
    )
    (net (code "72") (name "unconnected-(U1-P0.7-Pad4)") (class "Default")
      (node (ref "U1") (pin "4") (pinfunction "P0.7_4") (pintype "passive"))
    )
    (net (code "73") (name "unconnected-(U1-P1.7{slash}ADC7{slash}TxD_3{slash}XTALI-Pad11)") (class "Default")
      (node (ref "U1") (pin "11") (pinfunction "P1.7/ADC7/TxD_3/XTALI_11") (pintype "passive"))
    )
    (net (code "74") (name "unconnected-(U1-P2.6-Pad39)") (class "Default")
      (node (ref "U1") (pin "39") (pinfunction "P2.6_39") (pintype "passive"))
    )
    (net (code "75") (name "unconnected-(U1-P2.7-Pad40)") (class "Default")
      (node (ref "U1") (pin "40") (pinfunction "P2.7_40") (pintype "passive"))
    )
    (net (code "76") (name "unconnected-(U1-P3.4{slash}T0-Pad23)") (class "Default")
      (node (ref "U1") (pin "23") (pinfunction "P3.4/T0_23") (pintype "passive"))
    )
    (net (code "77") (name "unconnected-(U1-P3.5{slash}T1-Pad26)") (class "Default")
      (node (ref "U1") (pin "26") (pinfunction "P3.5/T1_26") (pintype "passive"))
    )
    (net (code "78") (name "unconnected-(U1-P4.2-Pad30)") (class "Default")
      (node (ref "U1") (pin "30") (pinfunction "P4.2_30") (pintype "passive"))
    )
    (net (code "79") (name "unconnected-(U1-P4.4-Pad32)") (class "Default")
      (node (ref "U1") (pin "32") (pinfunction "P4.4_32") (pintype "passive"))
    )
    (net (code "80") (name "unconnected-(U1-P4.5-Pad41)") (class "Default")
      (node (ref "U1") (pin "41") (pinfunction "P4.5_41") (pintype "passive"))
    )
    (net (code "81") (name "unconnected-(U1-P5.0{slash}RxD3_2-Pad24)") (class "Default")
      (node (ref "U1") (pin "24") (pinfunction "P5.0/RxD3_2_24") (pintype "passive"))
    )
    (net (code "82") (name "unconnected-(U1-P5.1{slash}TxD3_2-Pad25)") (class "Default")
      (node (ref "U1") (pin "25") (pinfunction "P5.1/TxD3_2_25") (pintype "passive"))
    )
    (net (code "83") (name "unconnected-(U1-P5.2{slash}RxD4_2-Pad48)") (class "Default")
      (node (ref "U1") (pin "48") (pinfunction "P5.2/RxD4_2_48") (pintype "passive"))
    )
    (net (code "84") (name "unconnected-(U1-P5.3-Pad1)") (class "Default")
      (node (ref "U1") (pin "1") (pinfunction "P5.3_1") (pintype "passive"))
    )
    (net (code "85") (name "unconnected-(U3-NC-Pad4)") (class "Default")
      (node (ref "U3") (pin "4") (pinfunction "NC_4") (pintype "passive+no_connect"))
    )
    (net (code "86") (name "unconnected-(U4-NC-Pad4)") (class "Default")
      (node (ref "U4") (pin "4") (pinfunction "NC_4") (pintype "passive+no_connect"))
    )
  )
)
